# G1000_Com_Switch.net
KiCad netlist of a schematic drawn in EasyEDA
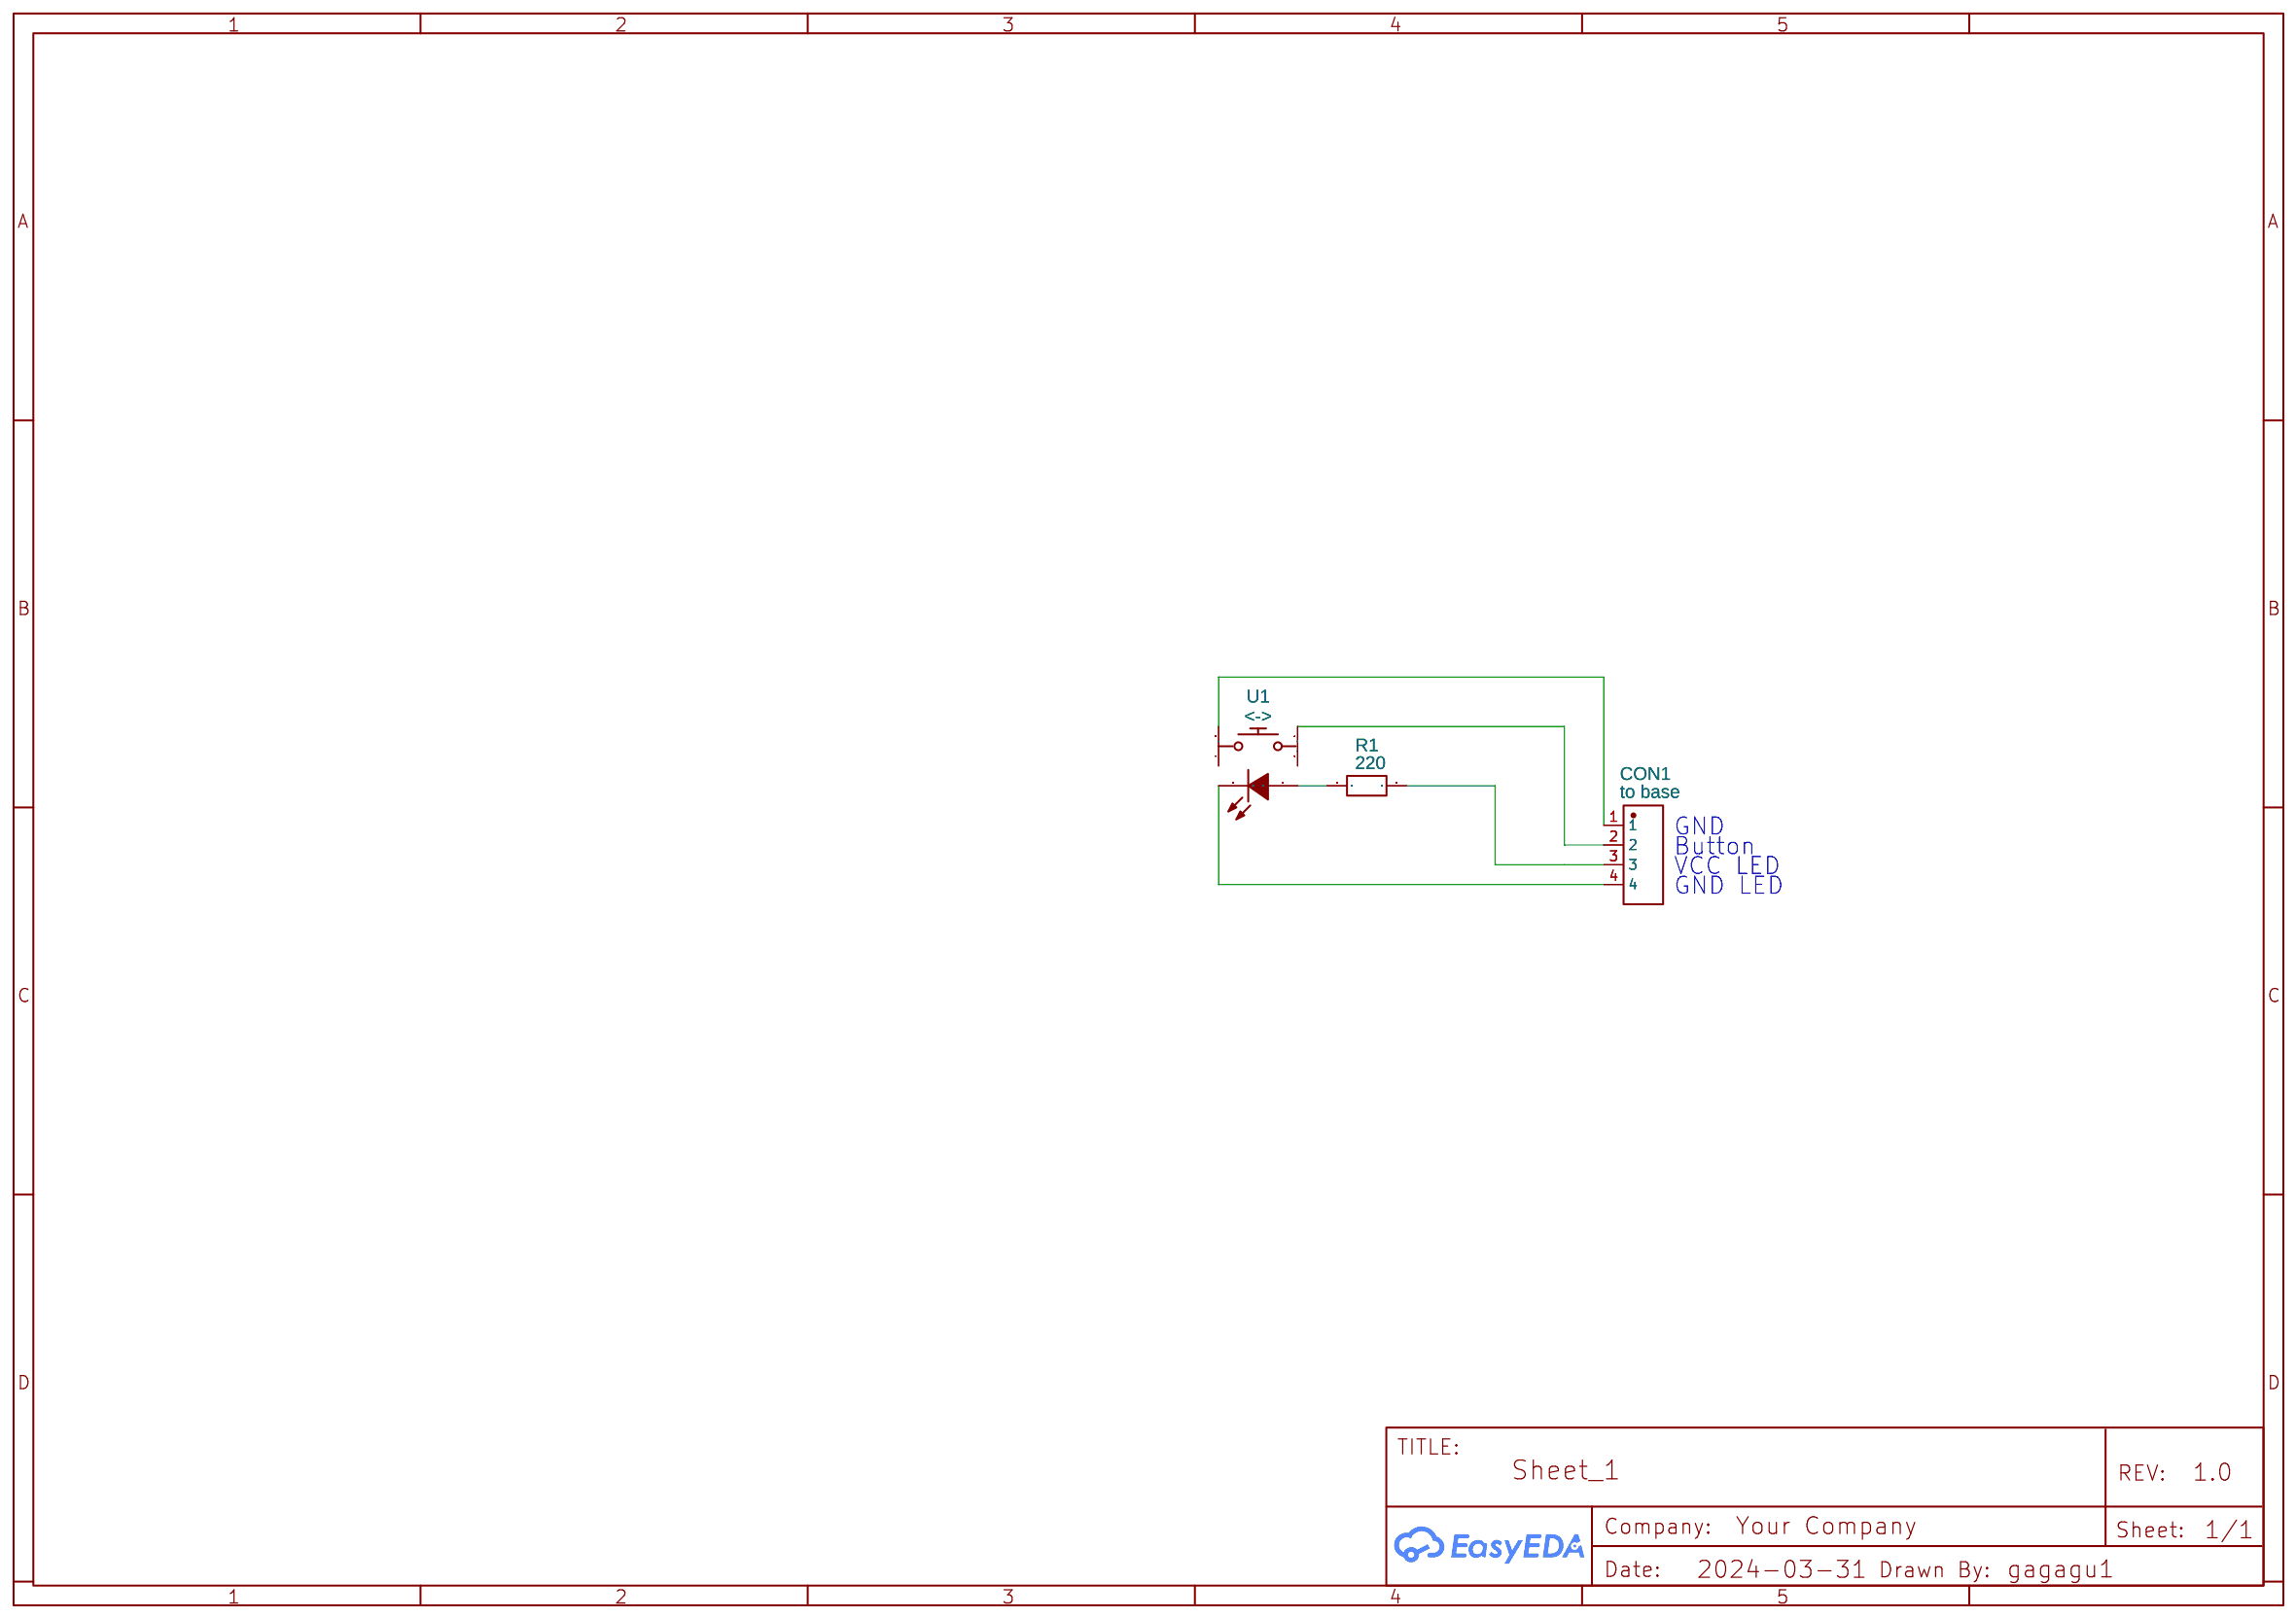
[diagram p0: schematic sheet]

(export (version "E")
  (design (tool "Eeschema 10.0.6"))
  (components
    (comp (ref "CON1")
      (value "to base")
      (fields
        (field (name "Manufacturer Part") "A2541HWV-4P")
        (field (name "Manufacturer") "Changjiang Connectors")
      )
      (libsource (lib "") (part "1X4PIN"))
    )
    (comp (ref "R1") (value "220") (libsource (lib "") (part "R_AXIAL-0.4_EU")))
    (comp (ref "U1") (value "<->") (libsource (lib "") (part "6X6_LED+PUSHBUTTON V2")))
  )
  (nets
    (net (code "1") (name "Net-(CON1-Pad1)") (class "Default")
      (node (ref "CON1") (pin "1") (pinfunction "1_1") (pintype "unspecified"))
      (node (ref "U1") (pin "3") (pinfunction "3_3") (pintype "unspecified"))
    )
    (net (code "2") (name "Net-(CON1-Pad2)") (class "Default")
      (node (ref "CON1") (pin "2") (pinfunction "2_2") (pintype "unspecified"))
      (node (ref "U1") (pin "1") (pinfunction "1_1") (pintype "unspecified"))
    )
    (net (code "3") (name "Net-(CON1-Pad3)") (class "Default")
      (node (ref "CON1") (pin "3") (pinfunction "3_3") (pintype "unspecified"))
      (node (ref "R1") (pin "1") (pinfunction "1_1") (pintype "unspecified"))
    )
    (net (code "4") (name "Net-(CON1-Pad4)") (class "Default")
      (node (ref "CON1") (pin "4") (pinfunction "4_4") (pintype "unspecified"))
      (node (ref "U1") (pin "C") (pinfunction "C_C") (pintype "unspecified"))
    )
    (net (code "5") (name "Net-(R1-Pad2)") (class "Default")
      (node (ref "R1") (pin "2") (pinfunction "2_2") (pintype "unspecified"))
      (node (ref "U1") (pin "A") (pinfunction "A_A") (pintype "unspecified"))
    )
    (net (code "6") (name "unconnected-(U1-Pad2)") (class "Default")
      (node (ref "U1") (pin "2") (pinfunction "2_2") (pintype "unspecified"))
    )
    (net (code "7") (name "unconnected-(U1-Pad4)") (class "Default")
      (node (ref "U1") (pin "4") (pinfunction "4_4") (pintype "unspecified"))
    )
  )
)
